# VOC_eCO2_Gas_Sensor.net
KiCad netlist of a schematic drawn in EAGLE
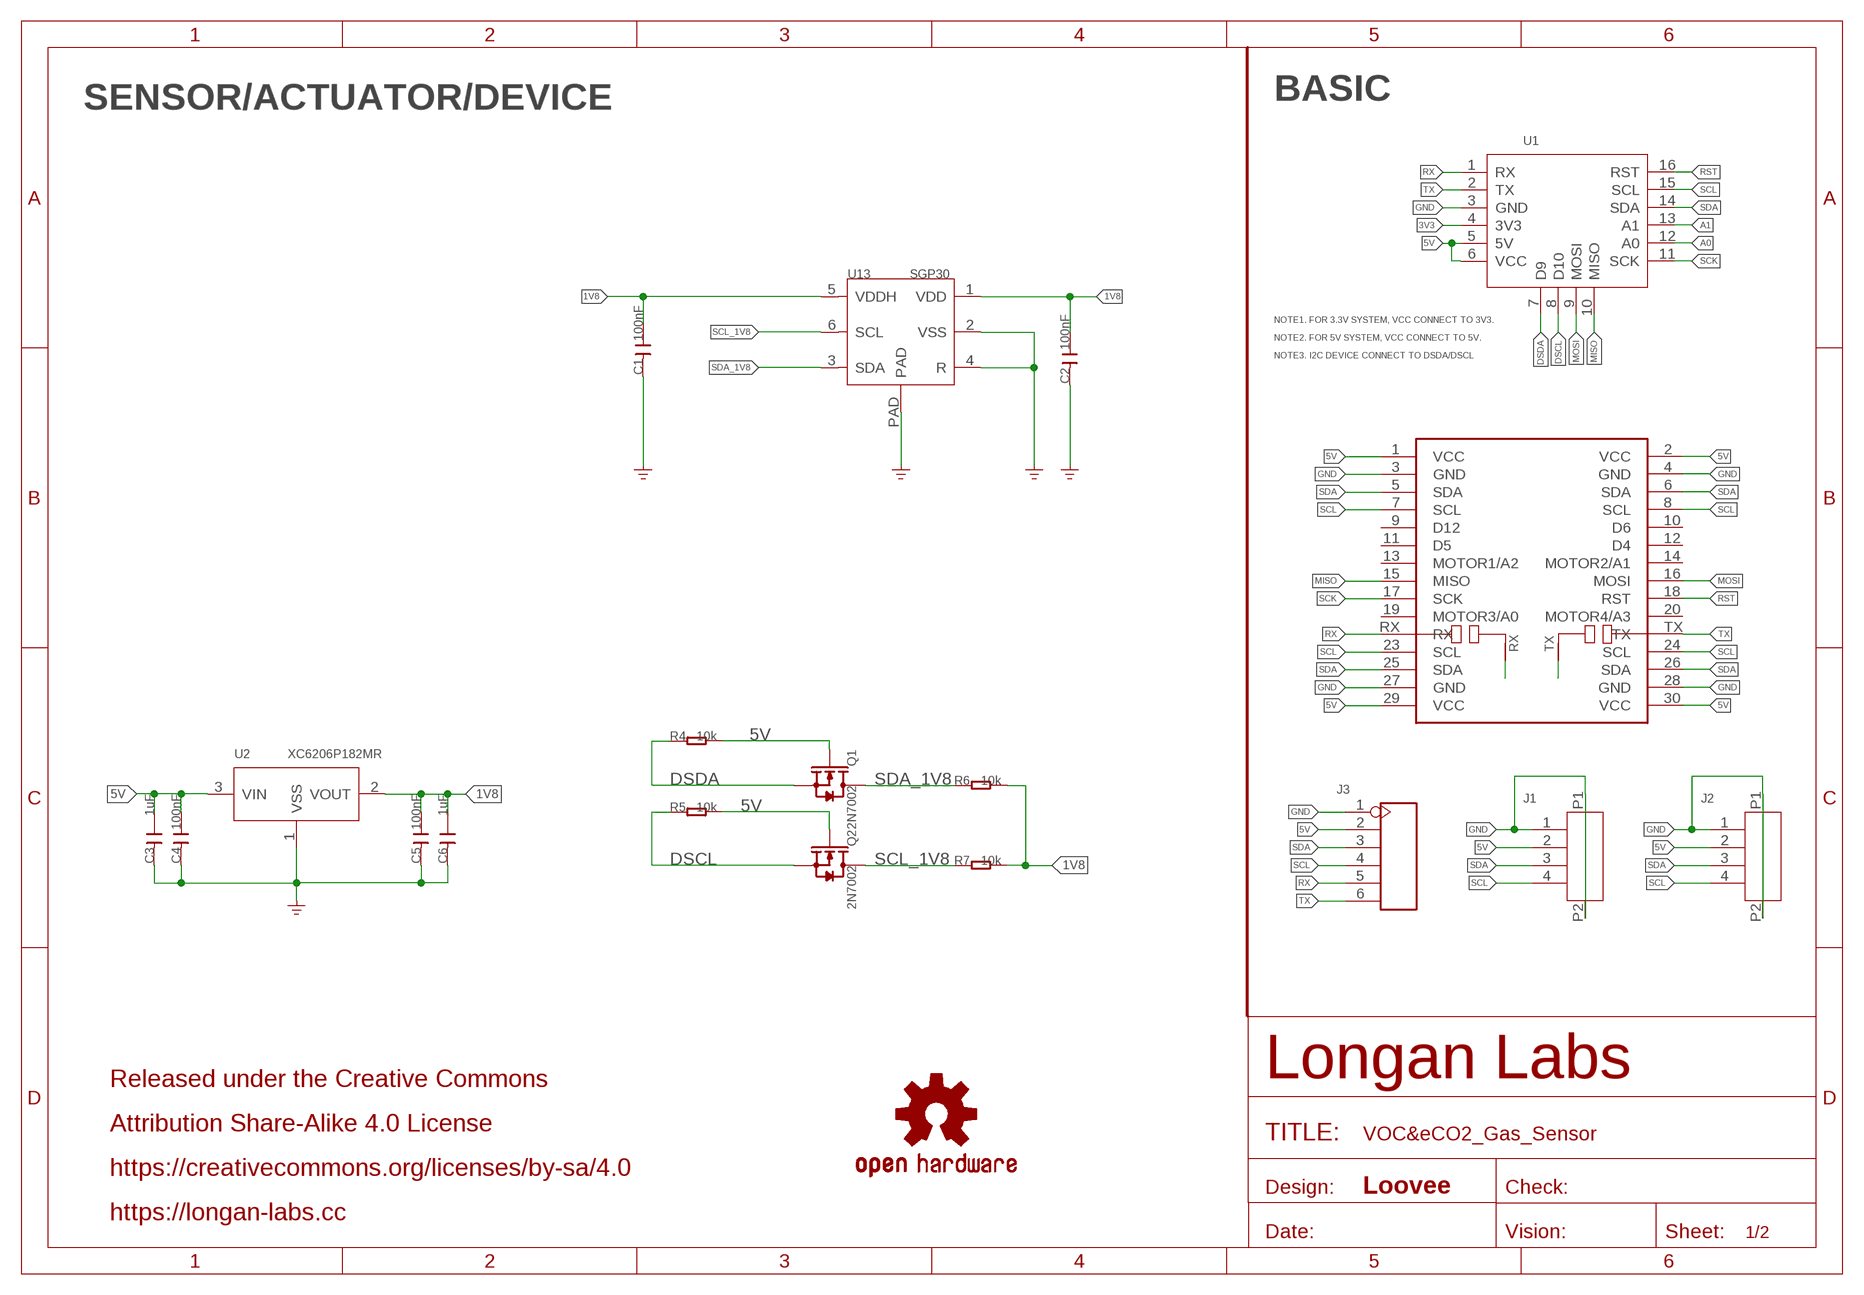
[diagram p0: schematic, sheet 1]

(export (version "E")
  (design (tool "Eeschema 10.0.6"))
  (components
    (comp (ref "C1")
      (value "100nF")
      (footprint "eagle-import:C0603")
      (libsource (lib "eagle-import") (part "CAP-0603"))
    )
    (comp (ref "C2")
      (value "100nF")
      (footprint "eagle-import:C0603")
      (libsource (lib "eagle-import") (part "CAP-0603"))
    )
    (comp (ref "C3")
      (value "1uF")
      (footprint "eagle-import:C0603")
      (libsource (lib "eagle-import") (part "CAP-0603"))
    )
    (comp (ref "C4")
      (value "100nF")
      (footprint "eagle-import:C0603")
      (libsource (lib "eagle-import") (part "CAP-0603"))
    )
    (comp (ref "C5")
      (value "100nF")
      (footprint "eagle-import:C0603")
      (libsource (lib "eagle-import") (part "CAP-0603"))
    )
    (comp (ref "C6")
      (value "1uF")
      (footprint "eagle-import:C0603")
      (libsource (lib "eagle-import") (part "CAP-0603"))
    )
    (comp (ref "J1")
      (value "HEADER-4P-1.0")
      (footprint "eagle-import:4P-1.0-90D")
      (libsource (lib "eagle-import") (part "HEADER-4P-1.0"))
    )
    (comp (ref "J2")
      (value "HEADER-4P-1.0")
      (footprint "eagle-import:4P-1.0-90D")
      (libsource (lib "eagle-import") (part "HEADER-4P-1.0"))
    )
    (comp (ref "J3")
      (value "HEADER-6P-55/35MIL")
      (footprint "eagle-import:H6-2.54")
      (libsource (lib "eagle-import") (part "HEADER-6P-55/35MIL"))
    )
    (comp (ref "LOGO2")
      (value "OSHW-LOGOS")
      (footprint "eagle-import:OSHW-LOGO-S")
      (libsource (lib "eagle-import") (part "OSHW-LOGOS"))
    )
    (comp (ref "MOUDLE2")
      (value "MOUDLE-CARDS-UART'BOARD'")
      (footprint "eagle-import:MOUDLE-2X15P-UART")
      (libsource (lib "eagle-import") (part "MOUDLE-CARDS-UART'BOARD'"))
    )
    (comp (ref "Q1")
      (value "2N7002")
      (footprint "eagle-import:SOT23")
      (libsource (lib "eagle-import") (part "MOSFET-N'SOT23'"))
    )
    (comp (ref "Q2")
      (value "2N7002")
      (footprint "eagle-import:SOT23")
      (libsource (lib "eagle-import") (part "MOSFET-N'SOT23'"))
    )
    (comp (ref "R4")
      (value "10k")
      (footprint "eagle-import:R0603")
      (libsource (lib "eagle-import") (part "R-0603"))
    )
    (comp (ref "R5")
      (value "10k")
      (footprint "eagle-import:R0603")
      (libsource (lib "eagle-import") (part "R-0603"))
    )
    (comp (ref "R6")
      (value "10k")
      (footprint "eagle-import:R0603")
      (libsource (lib "eagle-import") (part "R-0603"))
    )
    (comp (ref "R7")
      (value "10k")
      (footprint "eagle-import:R0603")
      (libsource (lib "eagle-import") (part "R-0603"))
    )
    (comp (ref "U1")
      (value "MOUDLE-CARDS")
      (footprint "eagle-import:16P-2.0-CARDS")
      (libsource (lib "eagle-import") (part "MOUDLE-CARDS"))
    )
    (comp (ref "U2")
      (value "XC6206P182MR")
      (footprint "eagle-import:SOT-23")
      (libsource (lib "eagle-import") (part "PMIC-XC6206PMR"))
    )
    (comp (ref "U13")
      (value "SGP30")
      (footprint "eagle-import:DFN6-0.8-2.45X2.45X0.9MM")
      (libsource (lib "eagle-import") (part "SENSOR-GAS-SGP30"))
    )
  )
  (nets
    (net (code "1") (name "1V8") (class "Default")
      (node (ref "C1") (pin "1") (pinfunction "1_1") (pintype "passive"))
      (node (ref "C2") (pin "1") (pinfunction "1_1") (pintype "passive"))
      (node (ref "C5") (pin "1") (pinfunction "1_1") (pintype "passive"))
      (node (ref "C6") (pin "1") (pinfunction "1_1") (pintype "passive"))
      (node (ref "R6") (pin "2") (pinfunction "2_2") (pintype "passive"))
      (node (ref "R7") (pin "2") (pinfunction "2_2") (pintype "passive"))
      (node (ref "U13") (pin "1") (pinfunction "VDD_1") (pintype "bidirectional"))
      (node (ref "U13") (pin "5") (pinfunction "VDDH_5") (pintype "bidirectional"))
      (node (ref "U2") (pin "2") (pinfunction "VOUT_2") (pintype "bidirectional"))
    )
    (net (code "2") (name "3V3") (class "Default")
      (node (ref "U1") (pin "4") (pinfunction "3V3_4") (pintype "bidirectional"))
    )
    (net (code "3") (name "5V") (class "Default")
      (node (ref "C3") (pin "1") (pinfunction "1_1") (pintype "passive"))
      (node (ref "C4") (pin "1") (pinfunction "1_1") (pintype "passive"))
      (node (ref "J1") (pin "2") (pinfunction "2_2") (pintype "bidirectional"))
      (node (ref "J2") (pin "2") (pinfunction "2_2") (pintype "bidirectional"))
      (node (ref "J3") (pin "2") (pinfunction "2_2") (pintype "bidirectional"))
      (node (ref "MOUDLE2") (pin "1") (pinfunction "VCC_1") (pintype "bidirectional"))
      (node (ref "MOUDLE2") (pin "2") (pinfunction "VCC_2") (pintype "bidirectional"))
      (node (ref "MOUDLE2") (pin "29") (pinfunction "VCC_29") (pintype "bidirectional"))
      (node (ref "MOUDLE2") (pin "30") (pinfunction "VCC_30") (pintype "bidirectional"))
      (node (ref "Q1") (pin "1") (pinfunction "G_1") (pintype "passive"))
      (node (ref "Q2") (pin "1") (pinfunction "G_1") (pintype "passive"))
      (node (ref "R4") (pin "2") (pinfunction "2_2") (pintype "passive"))
      (node (ref "R5") (pin "2") (pinfunction "2_2") (pintype "passive"))
      (node (ref "U1") (pin "5") (pinfunction "5V_5") (pintype "bidirectional"))
      (node (ref "U1") (pin "6") (pinfunction "VCC_6") (pintype "bidirectional"))
      (node (ref "U2") (pin "3") (pinfunction "VIN_3") (pintype "bidirectional"))
    )
    (net (code "4") (name "A0") (class "Default")
      (node (ref "U1") (pin "12") (pinfunction "A0_12") (pintype "bidirectional"))
    )
    (net (code "5") (name "A1") (class "Default")
      (node (ref "U1") (pin "13") (pinfunction "A1_13") (pintype "bidirectional"))
    )
    (net (code "6") (name "DSCL") (class "Default")
      (node (ref "Q2") (pin "2") (pinfunction "S_2") (pintype "passive"))
      (node (ref "R5") (pin "1") (pinfunction "1_1") (pintype "passive"))
      (node (ref "U1") (pin "8") (pinfunction "D10_8") (pintype "bidirectional"))
    )
    (net (code "7") (name "DSDA") (class "Default")
      (node (ref "Q1") (pin "2") (pinfunction "S_2") (pintype "passive"))
      (node (ref "R4") (pin "1") (pinfunction "1_1") (pintype "passive"))
      (node (ref "U1") (pin "7") (pinfunction "D9_7") (pintype "bidirectional"))
    )
    (net (code "8") (name "GND") (class "Default")
      (node (ref "C1") (pin "2") (pinfunction "2_2") (pintype "passive"))
      (node (ref "C2") (pin "2") (pinfunction "2_2") (pintype "passive"))
      (node (ref "C3") (pin "2") (pinfunction "2_2") (pintype "passive"))
      (node (ref "C4") (pin "2") (pinfunction "2_2") (pintype "passive"))
      (node (ref "C5") (pin "2") (pinfunction "2_2") (pintype "passive"))
      (node (ref "C6") (pin "2") (pinfunction "2_2") (pintype "passive"))
      (node (ref "J1") (pin "1") (pinfunction "1_1") (pintype "bidirectional"))
      (node (ref "J1") (pin "P1") (pinfunction "P1_P1") (pintype "bidirectional"))
      (node (ref "J1") (pin "P2") (pinfunction "P2_P2") (pintype "bidirectional"))
      (node (ref "J2") (pin "1") (pinfunction "1_1") (pintype "bidirectional"))
      (node (ref "J2") (pin "P1") (pinfunction "P1_P1") (pintype "bidirectional"))
      (node (ref "J2") (pin "P2") (pinfunction "P2_P2") (pintype "bidirectional"))
      (node (ref "J3") (pin "1") (pinfunction "1_1") (pintype "bidirectional"))
      (node (ref "MOUDLE2") (pin "27") (pinfunction "GND_27") (pintype "bidirectional"))
      (node (ref "MOUDLE2") (pin "28") (pinfunction "GND_28") (pintype "bidirectional"))
      (node (ref "MOUDLE2") (pin "3") (pinfunction "GND_3") (pintype "bidirectional"))
      (node (ref "MOUDLE2") (pin "4") (pinfunction "GND_4") (pintype "bidirectional"))
      (node (ref "U1") (pin "3") (pinfunction "GND_3") (pintype "bidirectional"))
      (node (ref "U13") (pin "2") (pinfunction "VSS_2") (pintype "bidirectional"))
      (node (ref "U13") (pin "4") (pinfunction "R_4") (pintype "bidirectional"))
      (node (ref "U13") (pin "PAD") (pinfunction "PAD_PAD") (pintype "bidirectional"))
      (node (ref "U2") (pin "1") (pinfunction "VSS_1") (pintype "bidirectional"))
    )
    (net (code "9") (name "MISO") (class "Default")
      (node (ref "MOUDLE2") (pin "15") (pinfunction "MISO_15") (pintype "bidirectional"))
      (node (ref "U1") (pin "10") (pinfunction "MISO_10") (pintype "bidirectional"))
    )
    (net (code "10") (name "MOSI") (class "Default")
      (node (ref "MOUDLE2") (pin "16") (pinfunction "MOSI_16") (pintype "bidirectional"))
      (node (ref "U1") (pin "9") (pinfunction "MOSI_9") (pintype "bidirectional"))
    )
    (net (code "11") (name "Net-(MOUDLE2-RX{slash}N-PadRX{slash}N1)") (class "Default")
      (node (ref "MOUDLE2") (pin "RX/N1") (pinfunction "RX/N_RX/N1") (pintype "bidirectional"))
      (node (ref "MOUDLE2") (pin "RX/N2") (pinfunction "RX/N_RX/N2") (pintype "bidirectional"))
    )
    (net (code "12") (name "Net-(MOUDLE2-TX{slash}N-PadTX{slash}N1)") (class "Default")
      (node (ref "MOUDLE2") (pin "TX/N1") (pinfunction "TX/N_TX/N1") (pintype "bidirectional"))
      (node (ref "MOUDLE2") (pin "TX/N2") (pinfunction "TX/N_TX/N2") (pintype "bidirectional"))
    )
    (net (code "13") (name "RST") (class "Default")
      (node (ref "MOUDLE2") (pin "18") (pinfunction "RST_18") (pintype "bidirectional"))
      (node (ref "U1") (pin "16") (pinfunction "RST_16") (pintype "bidirectional"))
    )
    (net (code "14") (name "RX") (class "Default")
      (node (ref "J3") (pin "5") (pinfunction "5_5") (pintype "bidirectional"))
      (node (ref "MOUDLE2") (pin "RX") (pinfunction "RX_RX") (pintype "bidirectional"))
      (node (ref "U1") (pin "1") (pinfunction "RX_1") (pintype "bidirectional"))
    )
    (net (code "15") (name "SCK") (class "Default")
      (node (ref "MOUDLE2") (pin "17") (pinfunction "SCK_17") (pintype "bidirectional"))
      (node (ref "U1") (pin "11") (pinfunction "SCK_11") (pintype "bidirectional"))
    )
    (net (code "16") (name "SCL") (class "Default")
      (node (ref "J1") (pin "4") (pinfunction "4_4") (pintype "bidirectional"))
      (node (ref "J2") (pin "4") (pinfunction "4_4") (pintype "bidirectional"))
      (node (ref "J3") (pin "4") (pinfunction "4_4") (pintype "bidirectional"))
      (node (ref "MOUDLE2") (pin "23") (pinfunction "SCL_23") (pintype "bidirectional"))
      (node (ref "MOUDLE2") (pin "24") (pinfunction "SCL_24") (pintype "bidirectional"))
      (node (ref "MOUDLE2") (pin "7") (pinfunction "SCL_7") (pintype "bidirectional"))
      (node (ref "MOUDLE2") (pin "8") (pinfunction "SCL_8") (pintype "bidirectional"))
      (node (ref "U1") (pin "15") (pinfunction "SCL_15") (pintype "bidirectional"))
    )
    (net (code "17") (name "SCL_1V8") (class "Default")
      (node (ref "Q2") (pin "3") (pinfunction "D_3") (pintype "passive"))
      (node (ref "R7") (pin "1") (pinfunction "1_1") (pintype "passive"))
      (node (ref "U13") (pin "6") (pinfunction "SCL_6") (pintype "bidirectional"))
    )
    (net (code "18") (name "SDA") (class "Default")
      (node (ref "J1") (pin "3") (pinfunction "3_3") (pintype "bidirectional"))
      (node (ref "J2") (pin "3") (pinfunction "3_3") (pintype "bidirectional"))
      (node (ref "J3") (pin "3") (pinfunction "3_3") (pintype "bidirectional"))
      (node (ref "MOUDLE2") (pin "25") (pinfunction "SDA_25") (pintype "bidirectional"))
      (node (ref "MOUDLE2") (pin "26") (pinfunction "SDA_26") (pintype "bidirectional"))
      (node (ref "MOUDLE2") (pin "5") (pinfunction "SDA_5") (pintype "bidirectional"))
      (node (ref "MOUDLE2") (pin "6") (pinfunction "SDA_6") (pintype "bidirectional"))
      (node (ref "U1") (pin "14") (pinfunction "SDA_14") (pintype "bidirectional"))
    )
    (net (code "19") (name "SDA_1V8") (class "Default")
      (node (ref "Q1") (pin "3") (pinfunction "D_3") (pintype "passive"))
      (node (ref "R6") (pin "1") (pinfunction "1_1") (pintype "passive"))
      (node (ref "U13") (pin "3") (pinfunction "SDA_3") (pintype "bidirectional"))
    )
    (net (code "20") (name "TX") (class "Default")
      (node (ref "J3") (pin "6") (pinfunction "6_6") (pintype "bidirectional"))
      (node (ref "MOUDLE2") (pin "TX") (pinfunction "TX_TX") (pintype "bidirectional"))
      (node (ref "U1") (pin "2") (pinfunction "TX_2") (pintype "bidirectional"))
    )
    (net (code "21") (name "unconnected-(MOUDLE2-D4-Pad12)") (class "Default")
      (node (ref "MOUDLE2") (pin "12") (pinfunction "D4_12") (pintype "bidirectional"))
    )
    (net (code "22") (name "unconnected-(MOUDLE2-D5-Pad11)") (class "Default")
      (node (ref "MOUDLE2") (pin "11") (pinfunction "D5_11") (pintype "bidirectional"))
    )
    (net (code "23") (name "unconnected-(MOUDLE2-D6-Pad10)") (class "Default")
      (node (ref "MOUDLE2") (pin "10") (pinfunction "D6_10") (pintype "bidirectional"))
    )
    (net (code "24") (name "unconnected-(MOUDLE2-D12-Pad9)") (class "Default")
      (node (ref "MOUDLE2") (pin "9") (pinfunction "D12_9") (pintype "bidirectional"))
    )
    (net (code "25") (name "unconnected-(MOUDLE2-MOTOR1{slash}A2-Pad13)") (class "Default")
      (node (ref "MOUDLE2") (pin "13") (pinfunction "MOTOR1/A2_13") (pintype "bidirectional"))
    )
    (net (code "26") (name "unconnected-(MOUDLE2-MOTOR2{slash}A1-Pad14)") (class "Default")
      (node (ref "MOUDLE2") (pin "14") (pinfunction "MOTOR2/A1_14") (pintype "bidirectional"))
    )
    (net (code "27") (name "unconnected-(MOUDLE2-MOTOR3{slash}A0-Pad19)") (class "Default")
      (node (ref "MOUDLE2") (pin "19") (pinfunction "MOTOR3/A0_19") (pintype "bidirectional"))
    )
    (net (code "28") (name "unconnected-(MOUDLE2-MOTOR4{slash}A3-Pad20)") (class "Default")
      (node (ref "MOUDLE2") (pin "20") (pinfunction "MOTOR4/A3_20") (pintype "bidirectional"))
    )
  )
)
